# AdcPmodWM8782.net
KiCad netlist of a schematic drawn in Altium Designer
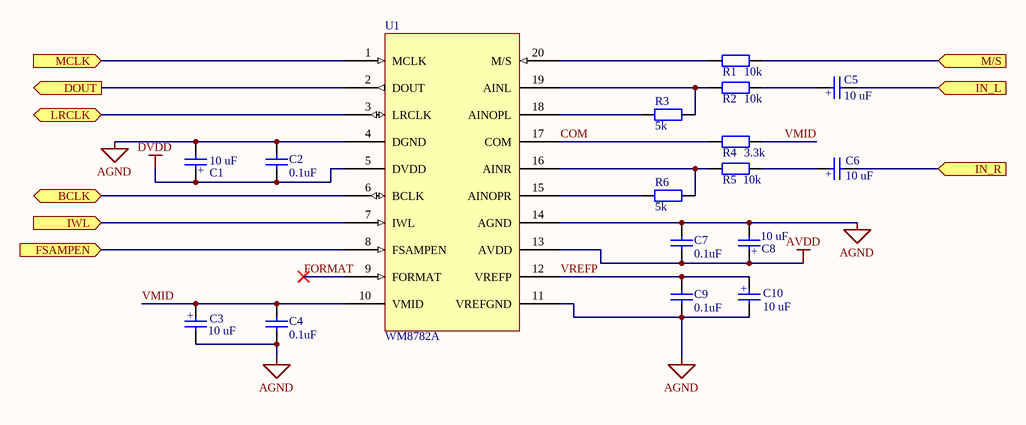
[diagram p0: AdcPmodWM8782.SchDoc]

(export (version "E")
  (design (tool "Eeschema 10.0.6"))
  (components
    (comp (ref "C1")
      (value "10 uF")
      (footprint "CAP_POL1206")
      (description "Capacitor Tantalum - Polymer")
      (fields
        (field (name "MANUFACTURER") "Vishay / Polytech")
        (field (name "MFR. PART NO.") "T55A106M010C0200")
      )
      (libsource (lib "AdcPmod") (part "CAP_POL"))
    )
    (comp (ref "C2")
      (value "0.1uF")
      (footprint "CAP0805")
      (description "Ceramic X7R")
      (fields (field (name "MANUFACTURER") "AVX") (field (name "MFR. PART NO.") "08055C104KAT2A"))
      (libsource (lib "AdcPmod") (part "CAP"))
    )
    (comp (ref "C3")
      (value "10 uF")
      (footprint "CAP_POL1206")
      (description "Capacitor Tantalum - Polymer")
      (fields
        (field (name "MANUFACTURER") "Vishay / Polytech")
        (field (name "MFR. PART NO.") "T55A106M010C0200")
      )
      (libsource (lib "AdcPmod") (part "CAP_POL"))
    )
    (comp (ref "C4")
      (value "0.1uF")
      (footprint "CAP0805")
      (description "Ceramic X7R")
      (fields (field (name "MANUFACTURER") "AVX") (field (name "MFR. PART NO.") "08055C104KAT2A"))
      (libsource (lib "AdcPmod") (part "CAP"))
    )
    (comp (ref "C5")
      (value "10 uF")
      (footprint "CAP EL SMD Dia. 5mm")
      (description "Electrolytic")
      (fields
        (field (name "MANUFACTURER") "United Chemi-Con")
        (field (name "MFR. PART NO.") "EMZJ250ADA220ME61G")
      )
      (libsource (lib "AdcPmod") (part "CAP_POL"))
    )
    (comp (ref "C6")
      (value "10 uF")
      (footprint "CAP EL SMD Dia. 5mm")
      (description "Electrolytic")
      (fields
        (field (name "MANUFACTURER") "United Chemi-Con")
        (field (name "MFR. PART NO.") "EMZJ250ADA220ME61G")
      )
      (libsource (lib "AdcPmod") (part "CAP_POL"))
    )
    (comp (ref "C7")
      (value "0.1uF")
      (footprint "CAP0805")
      (description "Ceramic X7R")
      (fields (field (name "MANUFACTURER") "AVX") (field (name "MFR. PART NO.") "08055C104KAT2A"))
      (libsource (lib "AdcPmod") (part "CAP"))
    )
    (comp (ref "C8")
      (value "10 uF")
      (footprint "CAP_POL1206")
      (description "Capacitor Tantalum - Polymer")
      (fields
        (field (name "MANUFACTURER") "Vishay / Polytech")
        (field (name "MFR. PART NO.") "T55A106M010C0200")
      )
      (libsource (lib "AdcPmod") (part "CAP_POL"))
    )
    (comp (ref "C9")
      (value "0.1uF")
      (footprint "CAP0805")
      (description "Ceramic X7R")
      (fields (field (name "MANUFACTURER") "AVX") (field (name "MFR. PART NO.") "08055C104KAT2A"))
      (libsource (lib "AdcPmod") (part "CAP"))
    )
    (comp (ref "C10")
      (value "10 uF")
      (footprint "CAP_POL1206")
      (description "Capacitor Tantalum - Polymer")
      (fields
        (field (name "MANUFACTURER") "Vishay / Polytech")
        (field (name "MFR. PART NO.") "T55A106M010C0200")
      )
      (libsource (lib "AdcPmod") (part "CAP_POL"))
    )
    (comp (ref "R1")
      (value "10k")
      (footprint "RES0805")
      (description "Thin Film")
      (fields (field (name "MANUFACTURER") "Vishay") (field (name "MFR. PART NO.") "TNPW080510K0FEEA"))
      (libsource (lib "AdcPmod") (part "RES"))
    )
    (comp (ref "R2")
      (value "10k")
      (footprint "RES0805")
      (description "Thin Film")
      (fields (field (name "MANUFACTURER") "Vishay") (field (name "MFR. PART NO.") "TNPW080510K0FEEA"))
      (libsource (lib "") (part "RES_1"))
    )
    (comp (ref "R3")
      (value "5k")
      (footprint "RES0805")
      (description "Thin Film")
      (fields (field (name "MANUFACTURER") "Vishay") (field (name "MFR. PART NO.") "TNPW12065K00BEEN"))
      (libsource (lib "AdcPmod") (part "RES"))
    )
    (comp (ref "R4")
      (value "3.3k")
      (footprint "RES0805")
      (description "Resistor")
      (libsource (lib "AdcPmod") (part "RES"))
    )
    (comp (ref "R5")
      (value "10k")
      (footprint "RES0805")
      (description "Thin Film")
      (fields (field (name "MANUFACTURER") "Vishay") (field (name "MFR. PART NO.") "TNPW080510K0FEEA"))
      (libsource (lib "AdcPmod") (part "RES"))
    )
    (comp (ref "R6")
      (value "5k")
      (footprint "RES0805")
      (description "Thin Film")
      (fields (field (name "MANUFACTURER") "Vishay") (field (name "MFR. PART NO.") "TNPW12065K00BEEN"))
      (libsource (lib "AdcPmod") (part "RES"))
    )
    (comp (ref "U1")
      (value "WM8782A")
      (footprint "SSOP16 5.3mm")
      (description "24-Bit, 192 kHz Stereo ADC")
      (fields (field (name "MANUFACTURER") "Cirrus Logic") (field (name "MFR. PART NO.") "WM8782SEDS/V"))
      (libsource (lib "AdcPmod") (part "WM8782"))
    )
  )
  (nets
    (net (code "1") (name "/BCLK") (class "Default")
      (node (ref "U1") (pin "6") (pinfunction "BCLK_6") (pintype "bidirectional"))
    )
    (net (code "2") (name "/COM") (class "Default")
      (node (ref "R4") (pin "1") (pinfunction "1_1") (pintype "passive"))
      (node (ref "U1") (pin "17") (pinfunction "COM_17") (pintype "passive"))
    )
    (net (code "3") (name "/DOUT") (class "Default")
      (node (ref "U1") (pin "2") (pinfunction "DOUT_2") (pintype "output"))
    )
    (net (code "4") (name "/FORMAT") (class "Default")
      (node (ref "U1") (pin "9") (pinfunction "FORMAT_9") (pintype "input+no_connect"))
    )
    (net (code "5") (name "/FSAMPEN") (class "Default")
      (node (ref "U1") (pin "8") (pinfunction "FSAMPEN_8") (pintype "input"))
    )
    (net (code "6") (name "/IN_L") (class "Default")
      (node (ref "C5") (pin "2") (pinfunction "2_2") (pintype "passive"))
    )
    (net (code "7") (name "/IN_R") (class "Default")
      (node (ref "C6") (pin "2") (pinfunction "2_2") (pintype "passive"))
    )
    (net (code "8") (name "/IWL") (class "Default")
      (node (ref "U1") (pin "7") (pinfunction "IWL_7") (pintype "input"))
    )
    (net (code "9") (name "/LRCLK") (class "Default")
      (node (ref "U1") (pin "3") (pinfunction "LRCLK_3") (pintype "bidirectional"))
    )
    (net (code "10") (name "/MCLK") (class "Default")
      (node (ref "U1") (pin "1") (pinfunction "MCLK_1") (pintype "input"))
    )
    (net (code "11") (name "/M{slash}S") (class "Default")
      (node (ref "R1") (pin "2") (pinfunction "2_2") (pintype "passive"))
    )
    (net (code "12") (name "/VMID") (class "Default")
      (node (ref "C3") (pin "1") (pinfunction "1_1") (pintype "passive"))
      (node (ref "C4") (pin "2") (pinfunction "2_2") (pintype "passive"))
      (node (ref "R4") (pin "2") (pinfunction "2_2") (pintype "passive"))
      (node (ref "U1") (pin "10") (pinfunction "VMID_10") (pintype "passive"))
    )
    (net (code "13") (name "/VREFP") (class "Default")
      (node (ref "C10") (pin "1") (pinfunction "1_1") (pintype "passive"))
      (node (ref "C9") (pin "2") (pinfunction "2_2") (pintype "passive"))
      (node (ref "U1") (pin "12") (pinfunction "VREFP_12") (pintype "passive"))
    )
    (net (code "14") (name "AGND") (class "Default")
      (node (ref "C1") (pin "2") (pinfunction "2_2") (pintype "passive"))
      (node (ref "C10") (pin "2") (pinfunction "2_2") (pintype "passive"))
      (node (ref "C2") (pin "2") (pinfunction "2_2") (pintype "passive"))
      (node (ref "C3") (pin "2") (pinfunction "2_2") (pintype "passive"))
      (node (ref "C4") (pin "1") (pinfunction "1_1") (pintype "passive"))
      (node (ref "C7") (pin "2") (pinfunction "2_2") (pintype "passive"))
      (node (ref "C8") (pin "2") (pinfunction "2_2") (pintype "passive"))
      (node (ref "C9") (pin "1") (pinfunction "1_1") (pintype "passive"))
      (node (ref "U1") (pin "11") (pinfunction "VREFGND_11") (pintype "power_in"))
      (node (ref "U1") (pin "14") (pinfunction "AGND_14") (pintype "power_in"))
      (node (ref "U1") (pin "4") (pinfunction "DGND_4") (pintype "power_in"))
    )
    (net (code "15") (name "AVDD") (class "Default")
      (node (ref "C7") (pin "1") (pinfunction "1_1") (pintype "passive"))
      (node (ref "C8") (pin "1") (pinfunction "1_1") (pintype "passive"))
      (node (ref "U1") (pin "13") (pinfunction "AVDD_13") (pintype "power_in"))
    )
    (net (code "16") (name "DVDD") (class "Default")
      (node (ref "C1") (pin "1") (pinfunction "1_1") (pintype "passive"))
      (node (ref "C2") (pin "1") (pinfunction "1_1") (pintype "passive"))
      (node (ref "U1") (pin "5") (pinfunction "DVDD_5") (pintype "power_in"))
    )
    (net (code "17") (name "Net-(C5-Pad1)") (class "Default")
      (node (ref "C5") (pin "1") (pinfunction "1_1") (pintype "passive"))
      (node (ref "R2") (pin "1") (pinfunction "1_1") (pintype "passive"))
    )
    (net (code "18") (name "Net-(C6-Pad1)") (class "Default")
      (node (ref "C6") (pin "1") (pinfunction "1_1") (pintype "passive"))
      (node (ref "R5") (pin "2") (pinfunction "2_2") (pintype "passive"))
    )
    (net (code "19") (name "Net-(U1-AINL)") (class "Default")
      (node (ref "R2") (pin "2") (pinfunction "2_2") (pintype "passive"))
      (node (ref "R3") (pin "2") (pinfunction "2_2") (pintype "passive"))
      (node (ref "U1") (pin "19") (pinfunction "AINL_19") (pintype "passive"))
    )
    (net (code "20") (name "Net-(U1-AINOPL)") (class "Default")
      (node (ref "R3") (pin "1") (pinfunction "1_1") (pintype "passive"))
      (node (ref "U1") (pin "18") (pinfunction "AINOPL_18") (pintype "passive"))
    )
    (net (code "21") (name "Net-(U1-AINOPR)") (class "Default")
      (node (ref "R6") (pin "1") (pinfunction "1_1") (pintype "passive"))
      (node (ref "U1") (pin "15") (pinfunction "AINOPR_15") (pintype "passive"))
    )
    (net (code "22") (name "Net-(U1-AINR)") (class "Default")
      (node (ref "R5") (pin "1") (pinfunction "1_1") (pintype "passive"))
      (node (ref "R6") (pin "2") (pinfunction "2_2") (pintype "passive"))
      (node (ref "U1") (pin "16") (pinfunction "AINR_16") (pintype "passive"))
    )
    (net (code "23") (name "Net-(U1-M{slash}S)") (class "Default")
      (node (ref "R1") (pin "1") (pinfunction "1_1") (pintype "passive"))
      (node (ref "U1") (pin "20") (pinfunction "M/S_20") (pintype "input"))
    )
  )
)
